# 3V3-CAN-UNISOLATED.net
KiCad netlist of a schematic drawn in Altium Designer
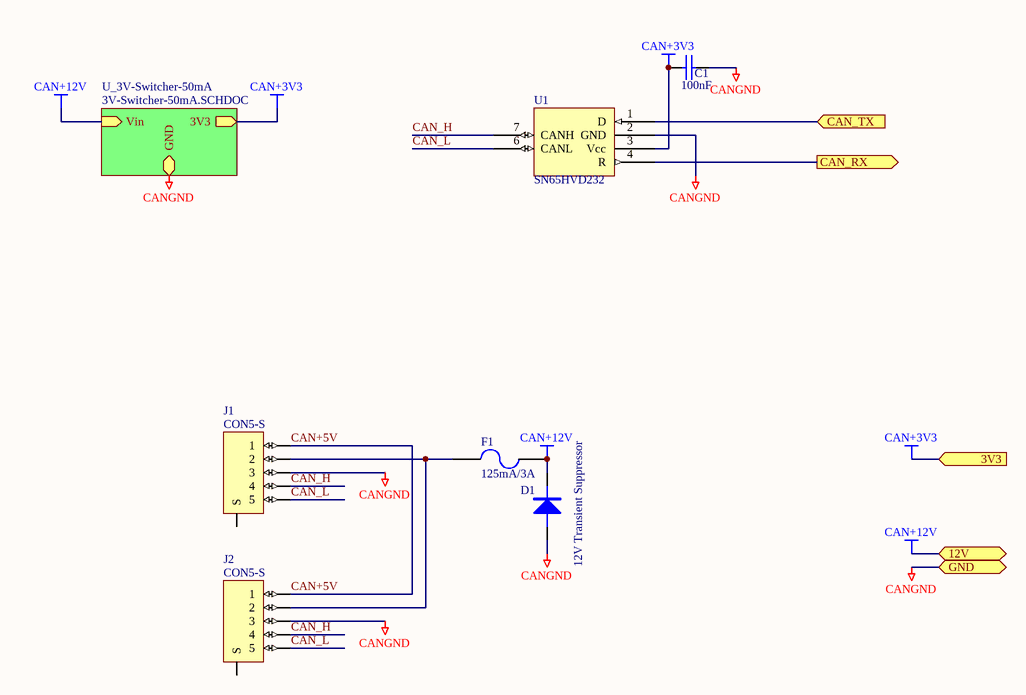
[diagram p0: 3V3-CAN-UNISOLATED.SchDoc]

(export (version "E")
  (design (tool "Eeschema 10.0.6"))
  (components
    (comp (ref "C1")
      (value "100nF")
      (footprint "0603")
      (description "Capacitor")
      (libsource (lib "*") (part "CAP"))
    )
    (comp (ref "D1")
      (value "12V Transient Suppressor")
      (footprint "SMA")
      (description "Diode")
      (libsource (lib "RCLDQ") (part "DIODE"))
    )
    (comp (ref "F1")
      (value "125mA/3A")
      (footprint "LITTELFUSE-154")
      (description "Fuse")
      (libsource (lib "*") (part "FUSE2"))
    )
    (comp (ref "J1")
      (value "CON5-S")
      (footprint "TRIAD5F")
      (description "Connector, 2 pin, with shield @ S")
      (libsource (lib "*") (part "CON5-S"))
    )
    (comp (ref "J2")
      (value "CON5-S")
      (footprint "TRIAD5F")
      (description "Connector, 2 pin, with shield @ S")
      (libsource (lib "*") (part "CON5-S"))
    )
    (comp (ref "U1")
      (value "SN65HVD232")
      (footprint "SO8")
      (description "3.3V CAN Transciever")
      (libsource (lib "*") (part "SN65HVD232"))
    )
  )
  (nets
    (net (code "1") (name "/CAN+5V") (class "Default")
      (node (ref "J1") (pin "1") (pinfunction "1_1") (pintype "bidirectional"))
      (node (ref "J2") (pin "1") (pinfunction "1_1") (pintype "bidirectional"))
    )
    (net (code "2") (name "/CAN_H") (class "Default")
      (node (ref "J1") (pin "4") (pinfunction "4_4") (pintype "bidirectional"))
      (node (ref "J2") (pin "4") (pinfunction "4_4") (pintype "bidirectional"))
      (node (ref "U1") (pin "7") (pinfunction "CANH_7") (pintype "bidirectional"))
    )
    (net (code "3") (name "/CAN_L") (class "Default")
      (node (ref "J1") (pin "5") (pinfunction "5_5") (pintype "bidirectional"))
      (node (ref "J2") (pin "5") (pinfunction "5_5") (pintype "bidirectional"))
      (node (ref "U1") (pin "6") (pinfunction "CANL_6") (pintype "bidirectional"))
    )
    (net (code "4") (name "/CAN_RX") (class "Default")
      (node (ref "U1") (pin "4") (pinfunction "R_4") (pintype "output"))
    )
    (net (code "5") (name "/CAN_TX") (class "Default")
      (node (ref "U1") (pin "1") (pinfunction "D_1") (pintype "input"))
    )
    (net (code "6") (name "CAN+3V3") (class "Default")
      (node (ref "C1") (pin "2") (pinfunction "2_2") (pintype "passive"))
      (node (ref "U1") (pin "3") (pinfunction "Vcc_3") (pintype "power_in"))
    )
    (net (code "7") (name "CAN+12V") (class "Default")
      (node (ref "D1") (pin "K") (pinfunction "K_K") (pintype "passive"))
      (node (ref "F1") (pin "2") (pinfunction "2_2") (pintype "passive"))
    )
    (net (code "8") (name "CANGND") (class "Default")
      (node (ref "C1") (pin "1") (pinfunction "1_1") (pintype "passive"))
      (node (ref "D1") (pin "A") (pinfunction "A_A") (pintype "passive"))
      (node (ref "J1") (pin "3") (pinfunction "3_3") (pintype "bidirectional"))
      (node (ref "J2") (pin "3") (pinfunction "3_3") (pintype "bidirectional"))
      (node (ref "U1") (pin "2") (pinfunction "GND_2") (pintype "power_in"))
    )
    (net (code "9") (name "Net-(F1-Pad1)") (class "Default")
      (node (ref "F1") (pin "1") (pinfunction "1_1") (pintype "passive"))
      (node (ref "J1") (pin "2") (pinfunction "2_2") (pintype "bidirectional"))
      (node (ref "J2") (pin "2") (pinfunction "2_2") (pintype "bidirectional"))
    )
    (net (code "10") (name "unconnected-(J1-S-Pad0)") (class "Default")
      (node (ref "J1") (pin "0") (pinfunction "S_0") (pintype "bidirectional"))
    )
    (net (code "11") (name "unconnected-(J2-S-Pad0)") (class "Default")
      (node (ref "J2") (pin "0") (pinfunction "S_0") (pintype "bidirectional"))
    )
  )
)
